# currentW_cond.net
KiCad netlist of a schematic drawn in Altium Designer
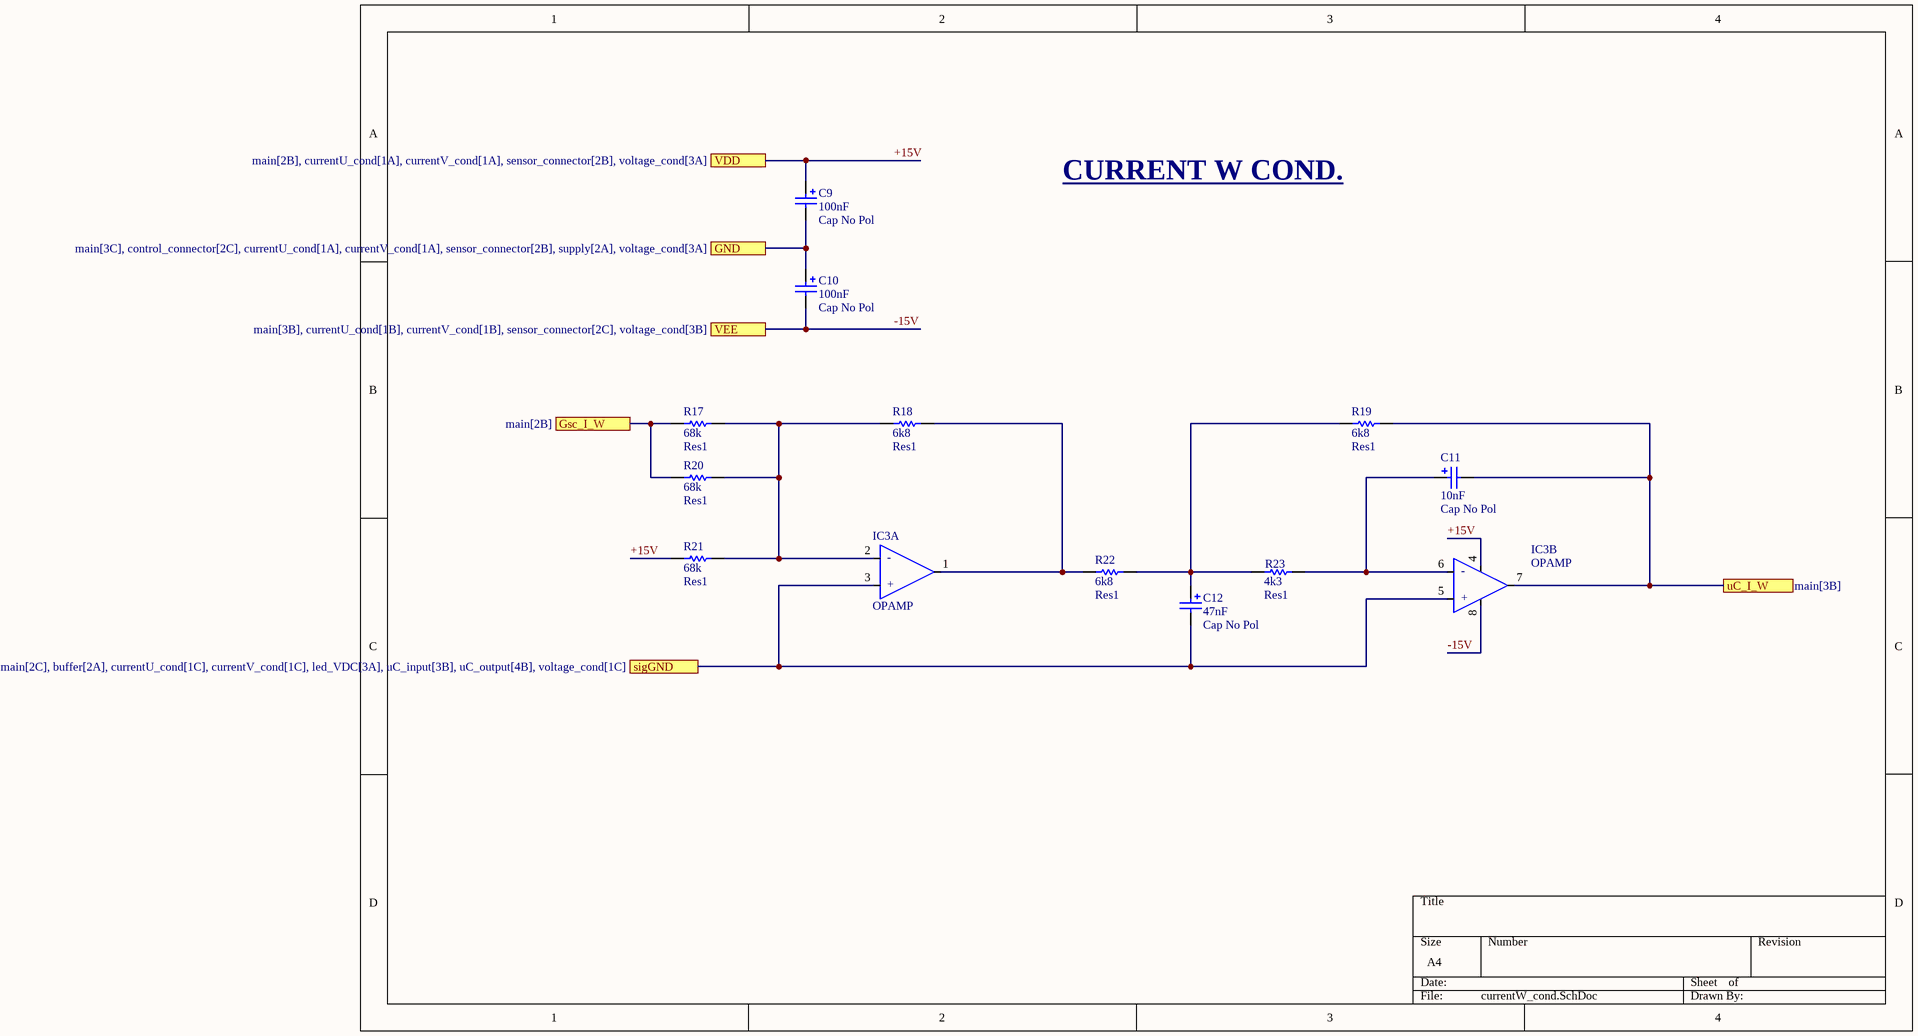
[diagram p0: currentW_cond.SchDoc]

(export (version "E")
  (design (tool "Eeschema 10.0.6"))
  (components
    (comp (ref "C9")
      (value "Cap No Pol")
      (footprint "RAD-0.1_mod")
      (description "Polarized Capacitor (Radial)")
      (fields (field (name "ALTIUM_VALUE") "100nF") (field (name "PUBLISHER") "Altium Limited"))
      (libsource (lib "LABSTEPS_Project") (part "Cap No Pol"))
    )
    (comp (ref "C10")
      (value "Cap No Pol")
      (footprint "RAD-0.1_mod")
      (description "Polarized Capacitor (Radial)")
      (fields (field (name "ALTIUM_VALUE") "100nF") (field (name "PUBLISHER") "Altium Limited"))
      (libsource (lib "LABSTEPS_Project") (part "Cap No Pol"))
    )
    (comp (ref "C11")
      (value "Cap No Pol")
      (footprint "RAD-0.1_mod")
      (description "Polarized Capacitor (Radial)")
      (fields (field (name "ALTIUM_VALUE") "10nF") (field (name "PUBLISHER") "Altium Limited"))
      (libsource (lib "LABSTEPS_Project") (part "Cap No Pol"))
    )
    (comp (ref "C12")
      (value "Cap No Pol")
      (footprint "RAD-0.1_mod")
      (description "Polarized Capacitor (Radial)")
      (fields (field (name "ALTIUM_VALUE") "47nF") (field (name "PUBLISHER") "Altium Limited"))
      (libsource (lib "LABSTEPS_Project") (part "Cap No Pol"))
    )
    (comp (ref "IC3")
      (value "OPAMP")
      (footprint "DIP-8_mod")
      (description "ADTL082")
      (libsource (lib "LABSTEPS_Project") (part "ADTL082"))
    )
    (comp (ref "R17")
      (value "Res1")
      (footprint "AXIAL-0.3_mod")
      (description "Resistor")
      (fields (field (name "ALTIUM_VALUE") "68k") (field (name "PUBLISHER") "Altium Limited"))
      (libsource (lib "LABSTEPS_Project") (part "Res1"))
    )
    (comp (ref "R18")
      (value "Res1")
      (footprint "AXIAL-0.3_mod")
      (description "Resistor")
      (fields (field (name "ALTIUM_VALUE") "6k8") (field (name "PUBLISHER") "Altium Limited"))
      (libsource (lib "LABSTEPS_Project") (part "Res1"))
    )
    (comp (ref "R19")
      (value "Res1")
      (footprint "AXIAL-0.3_mod")
      (description "Resistor")
      (fields (field (name "ALTIUM_VALUE") "6k8") (field (name "PUBLISHER") "Altium Limited"))
      (libsource (lib "LABSTEPS_Project") (part "Res1"))
    )
    (comp (ref "R20")
      (value "Res1")
      (footprint "AXIAL-0.3_mod")
      (description "Resistor")
      (fields (field (name "ALTIUM_VALUE") "68k") (field (name "PUBLISHER") "Altium Limited"))
      (libsource (lib "LABSTEPS_Project") (part "Res1"))
    )
    (comp (ref "R21")
      (value "Res1")
      (footprint "AXIAL-0.3_mod")
      (description "Resistor")
      (fields (field (name "ALTIUM_VALUE") "68k") (field (name "PUBLISHER") "Altium Limited"))
      (libsource (lib "LABSTEPS_Project") (part "Res1"))
    )
    (comp (ref "R22")
      (value "Res1")
      (footprint "AXIAL-0.3_mod")
      (description "Resistor")
      (fields (field (name "ALTIUM_VALUE") "6k8") (field (name "PUBLISHER") "Altium Limited"))
      (libsource (lib "LABSTEPS_Project") (part "Res1"))
    )
    (comp (ref "R23")
      (value "Res1")
      (footprint "AXIAL-0.3_mod")
      (description "Resistor")
      (fields (field (name "ALTIUM_VALUE") "4k3") (field (name "PUBLISHER") "Altium Limited"))
      (libsource (lib "LABSTEPS_Project") (part "Res1"))
    )
  )
  (nets
    (net (code "1") (name "/+15V") (class "Default")
      (node (ref "C9") (pin "1") (pinfunction "1_1") (pintype "passive"))
      (node (ref "IC3") (pin "4") (pinfunction "-V_4") (pintype "passive"))
      (node (ref "R21") (pin "1") (pinfunction "1_1") (pintype "passive"))
    )
    (net (code "2") (name "/-15V") (class "Default")
      (node (ref "C10") (pin "2") (pinfunction "2_2") (pintype "passive"))
      (node (ref "IC3") (pin "8") (pinfunction "V+_8") (pintype "passive"))
    )
    (net (code "3") (name "/GND") (class "Default")
      (node (ref "C10") (pin "1") (pinfunction "1_1") (pintype "passive"))
      (node (ref "C9") (pin "2") (pinfunction "2_2") (pintype "passive"))
    )
    (net (code "4") (name "/Gsc_I_W") (class "Default")
      (node (ref "R17") (pin "1") (pinfunction "1_1") (pintype "passive"))
      (node (ref "R20") (pin "1") (pinfunction "1_1") (pintype "passive"))
    )
    (net (code "5") (name "/sigGND") (class "Default")
      (node (ref "C12") (pin "2") (pinfunction "2_2") (pintype "passive"))
      (node (ref "IC3") (pin "3") (pinfunction "IN_A_+_3") (pintype "passive"))
      (node (ref "IC3") (pin "5") (pinfunction "IN_B_+_5") (pintype "passive"))
    )
    (net (code "6") (name "/uC_I_W") (class "Default")
      (node (ref "C11") (pin "2") (pinfunction "2_2") (pintype "passive"))
      (node (ref "IC3") (pin "7") (pinfunction "OUT_B_7") (pintype "passive"))
      (node (ref "R19") (pin "2") (pinfunction "2_2") (pintype "passive"))
    )
    (net (code "7") (name "Net-(C12-Pad1)") (class "Default")
      (node (ref "C12") (pin "1") (pinfunction "1_1") (pintype "passive"))
      (node (ref "R19") (pin "1") (pinfunction "1_1") (pintype "passive"))
      (node (ref "R22") (pin "2") (pinfunction "2_2") (pintype "passive"))
      (node (ref "R23") (pin "1") (pinfunction "1_1") (pintype "passive"))
    )
    (net (code "8") (name "Net-(IC3A-IN_A_-)") (class "Default")
      (node (ref "IC3") (pin "2") (pinfunction "IN_A_-_2") (pintype "passive"))
      (node (ref "R17") (pin "2") (pinfunction "2_2") (pintype "passive"))
      (node (ref "R18") (pin "1") (pinfunction "1_1") (pintype "passive"))
      (node (ref "R20") (pin "2") (pinfunction "2_2") (pintype "passive"))
      (node (ref "R21") (pin "2") (pinfunction "2_2") (pintype "passive"))
    )
    (net (code "9") (name "Net-(IC3A-OUT_A)") (class "Default")
      (node (ref "IC3") (pin "1") (pinfunction "OUT_A_1") (pintype "passive"))
      (node (ref "R18") (pin "2") (pinfunction "2_2") (pintype "passive"))
      (node (ref "R22") (pin "1") (pinfunction "1_1") (pintype "passive"))
    )
    (net (code "10") (name "Net-(IC3B-IN_B_-)") (class "Default")
      (node (ref "C11") (pin "1") (pinfunction "1_1") (pintype "passive"))
      (node (ref "IC3") (pin "6") (pinfunction "IN_B_-_6") (pintype "passive"))
      (node (ref "R23") (pin "2") (pinfunction "2_2") (pintype "passive"))
    )
  )
)
